# smarty03.net
KiCad netlist of a schematic drawn in EAGLE
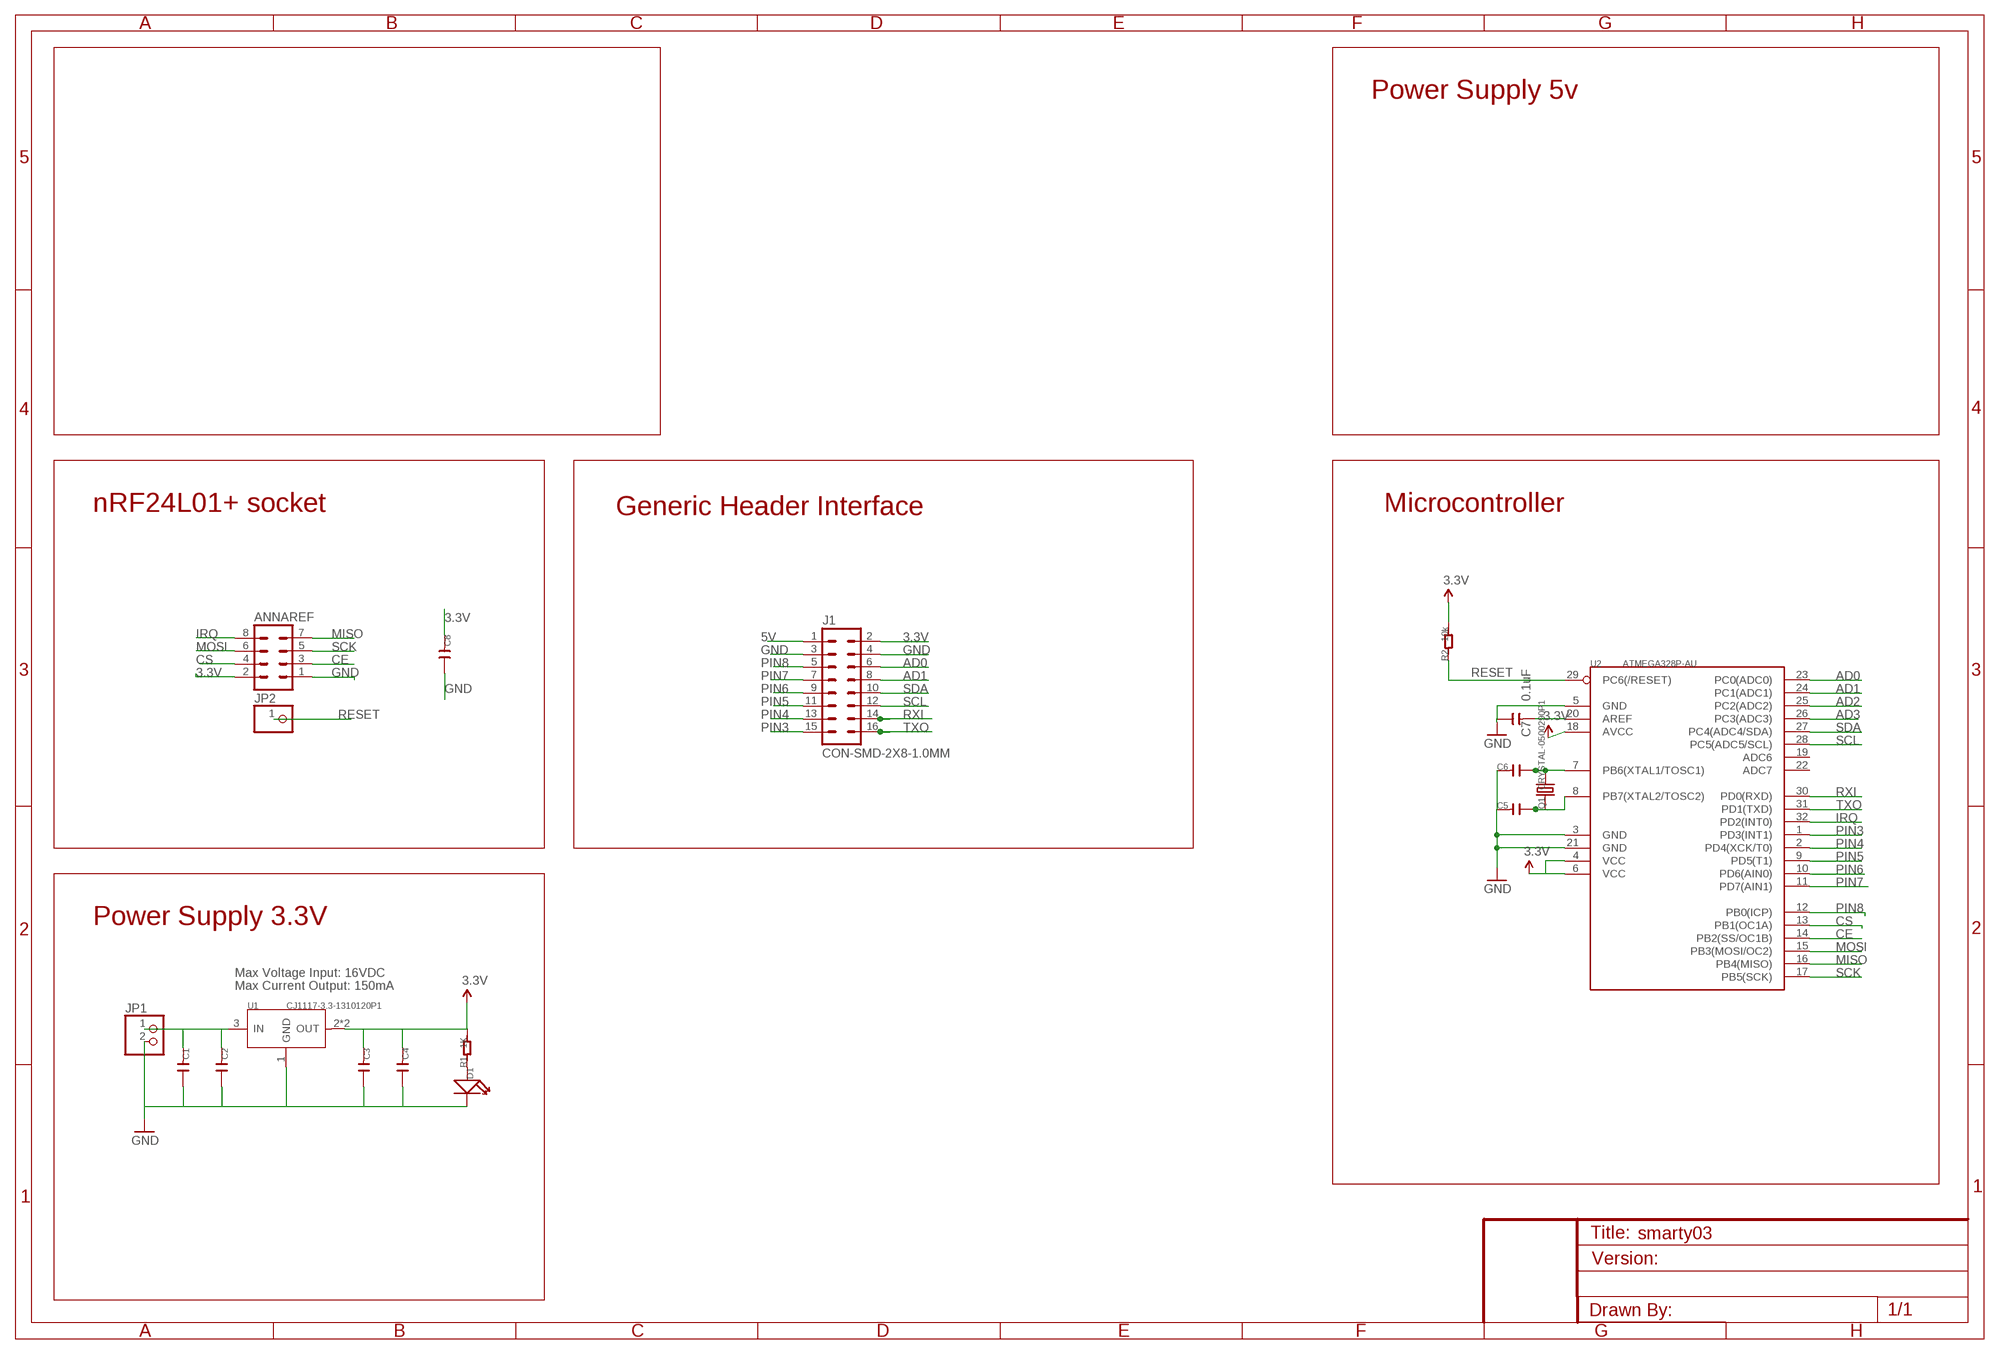
[diagram p0: schematic, sheet 1]

(export (version "E")
  (design (tool "Eeschema 10.0.6"))
  (components
    (comp (ref "ANNAREF")
      (value "MA04-2")
      (footprint "eagle-import:MA04-2")
      (libsource (lib "eagle-import") (part "MA04-2"))
    )
    (comp (ref "C1")
      (value "C-0603")
      (footprint "eagle-import:C0603")
      (libsource (lib "eagle-import") (part "C-0603"))
    )
    (comp (ref "C2")
      (value "C-0805")
      (footprint "eagle-import:C0805")
      (libsource (lib "eagle-import") (part "C-0805"))
    )
    (comp (ref "C3")
      (value "C-0603")
      (footprint "eagle-import:C0603")
      (libsource (lib "eagle-import") (part "C-0603"))
    )
    (comp (ref "C4")
      (value "C-0805")
      (footprint "eagle-import:C0805")
      (libsource (lib "eagle-import") (part "C-0805"))
    )
    (comp (ref "C5")
      (value "C-0603")
      (footprint "eagle-import:C0603")
      (libsource (lib "eagle-import") (part "C-0603"))
    )
    (comp (ref "C6")
      (value "C-0603")
      (footprint "eagle-import:C0603")
      (libsource (lib "eagle-import") (part "C-0603"))
    )
    (comp (ref "C7")
      (value "0.1uF")
      (footprint "eagle-import:C0805")
      (libsource (lib "eagle-import") (part "C-0805"))
    )
    (comp (ref "C8")
      (value "C-0805")
      (footprint "eagle-import:C0805")
      (libsource (lib "eagle-import") (part "C-0805"))
    )
    (comp (ref "D1")
      (value "LED")
      (footprint "eagle-import:LED0603")
      (libsource (lib "eagle-import") (part "LED"))
    )
    (comp (ref "J1")
      (value "CON-SMD-2X8-1.0MM")
      (footprint "eagle-import:SBH100-NBPC-D08")
      (libsource (lib "eagle-import") (part "CON-SMD-2X8-1.0MM"))
    )
    (comp (ref "JP1")
      (value "PINHD-1X2")
      (footprint "eagle-import:1X02")
      (libsource (lib "eagle-import") (part "PINHD-1X2"))
    )
    (comp (ref "JP2")
      (value "PINHD-1X1")
      (footprint "eagle-import:1X01")
      (libsource (lib "eagle-import") (part "PINHD-1X1"))
    )
    (comp (ref "Q1")
      (value "CRYSTAL-0500290P1")
      (footprint "eagle-import:2P-SMD-5.0X3.2")
      (libsource (lib "eagle-import") (part "CRYSTAL-0500290P1"))
    )
    (comp (ref "R1")
      (value "1K")
      (footprint "eagle-import:R0603")
      (libsource (lib "eagle-import") (part "R-0603"))
    )
    (comp (ref "R2")
      (value "10k")
      (footprint "eagle-import:R0603")
      (libsource (lib "eagle-import") (part "R-0603"))
    )
    (comp (ref "U1")
      (value "CJ1117-3.3-1310120P1")
      (footprint "eagle-import:SOT89")
      (libsource (lib "eagle-import") (part "CJ1117-3.3-1310120P1"))
    )
    (comp (ref "U2")
      (value "ATMEGA328P-AU")
      (footprint "eagle-import:TQFP32")
      (libsource (lib "eagle-import") (part "ATMEGA328P-AU-1030060P1"))
    )
  )
  (nets
    (net (code "1") (name "/5V") (class "Default")
      (node (ref "J1") (pin "1") (pinfunction "1_1") (pintype "passive"))
    )
    (net (code "2") (name "/AD0") (class "Default")
      (node (ref "J1") (pin "6") (pinfunction "6_6") (pintype "passive"))
      (node (ref "U2") (pin "23") (pinfunction "PC0(ADC0)_23") (pintype "bidirectional"))
    )
    (net (code "3") (name "/AD1") (class "Default")
      (node (ref "J1") (pin "8") (pinfunction "8_8") (pintype "passive"))
      (node (ref "U2") (pin "24") (pinfunction "PC1(ADC1)_24") (pintype "bidirectional"))
    )
    (net (code "4") (name "/AD2") (class "Default")
      (node (ref "U2") (pin "25") (pinfunction "PC2(ADC2)_25") (pintype "bidirectional"))
    )
    (net (code "5") (name "/AD3") (class "Default")
      (node (ref "U2") (pin "26") (pinfunction "PC3(ADC3)_26") (pintype "bidirectional"))
    )
    (net (code "6") (name "/CE") (class "Default")
      (node (ref "ANNAREF") (pin "3") (pinfunction "3_3") (pintype "passive"))
      (node (ref "U2") (pin "14") (pinfunction "PB2(SS/OC1B)_14") (pintype "bidirectional"))
    )
    (net (code "7") (name "/CS") (class "Default")
      (node (ref "ANNAREF") (pin "4") (pinfunction "4_4") (pintype "passive"))
      (node (ref "U2") (pin "13") (pinfunction "PB1(OC1A)_13") (pintype "bidirectional"))
    )
    (net (code "8") (name "/IRQ") (class "Default")
      (node (ref "ANNAREF") (pin "8") (pinfunction "8_8") (pintype "passive"))
      (node (ref "U2") (pin "32") (pinfunction "PD2(INT0)_32") (pintype "bidirectional"))
    )
    (net (code "9") (name "/MISO") (class "Default")
      (node (ref "ANNAREF") (pin "7") (pinfunction "7_7") (pintype "passive"))
      (node (ref "U2") (pin "16") (pinfunction "PB4(MISO)_16") (pintype "bidirectional"))
    )
    (net (code "10") (name "/MOSI") (class "Default")
      (node (ref "ANNAREF") (pin "6") (pinfunction "6_6") (pintype "passive"))
      (node (ref "U2") (pin "15") (pinfunction "PB3(MOSI/OC2)_15") (pintype "bidirectional"))
    )
    (net (code "11") (name "/PIN3") (class "Default")
      (node (ref "J1") (pin "15") (pinfunction "15_15") (pintype "passive"))
      (node (ref "U2") (pin "1") (pinfunction "PD3(INT1)_1") (pintype "bidirectional"))
    )
    (net (code "12") (name "/PIN4") (class "Default")
      (node (ref "J1") (pin "13") (pinfunction "13_13") (pintype "passive"))
      (node (ref "U2") (pin "2") (pinfunction "PD4(XCK/T0)_2") (pintype "bidirectional"))
    )
    (net (code "13") (name "/PIN5") (class "Default")
      (node (ref "J1") (pin "11") (pinfunction "11_11") (pintype "passive"))
      (node (ref "U2") (pin "9") (pinfunction "PD5(T1)_9") (pintype "bidirectional"))
    )
    (net (code "14") (name "/PIN6") (class "Default")
      (node (ref "J1") (pin "9") (pinfunction "9_9") (pintype "passive"))
      (node (ref "U2") (pin "10") (pinfunction "PD6(AIN0)_10") (pintype "bidirectional"))
    )
    (net (code "15") (name "/PIN7") (class "Default")
      (node (ref "J1") (pin "7") (pinfunction "7_7") (pintype "passive"))
      (node (ref "U2") (pin "11") (pinfunction "PD7(AIN1)_11") (pintype "bidirectional"))
    )
    (net (code "16") (name "/PIN8") (class "Default")
      (node (ref "J1") (pin "5") (pinfunction "5_5") (pintype "passive"))
      (node (ref "U2") (pin "12") (pinfunction "PB0(ICP)_12") (pintype "bidirectional"))
    )
    (net (code "17") (name "/RESET") (class "Default")
      (node (ref "JP2") (pin "1") (pinfunction "1_1") (pintype "passive"))
      (node (ref "R2") (pin "1") (pinfunction "1_1") (pintype "bidirectional"))
      (node (ref "U2") (pin "29") (pinfunction "PC6(/RESET)_29") (pintype "bidirectional"))
    )
    (net (code "18") (name "/RXI") (class "Default")
      (node (ref "J1") (pin "14") (pinfunction "14_14") (pintype "passive"))
      (node (ref "U2") (pin "30") (pinfunction "PD0(RXD)_30") (pintype "bidirectional"))
    )
    (net (code "19") (name "/SCK") (class "Default")
      (node (ref "ANNAREF") (pin "5") (pinfunction "5_5") (pintype "passive"))
      (node (ref "U2") (pin "17") (pinfunction "PB5(SCK)_17") (pintype "bidirectional"))
    )
    (net (code "20") (name "/SCL") (class "Default")
      (node (ref "J1") (pin "12") (pinfunction "12_12") (pintype "passive"))
      (node (ref "U2") (pin "28") (pinfunction "PC5(ADC5/SCL)_28") (pintype "bidirectional"))
    )
    (net (code "21") (name "/SDA") (class "Default")
      (node (ref "J1") (pin "10") (pinfunction "10_10") (pintype "passive"))
      (node (ref "U2") (pin "27") (pinfunction "PC4(ADC4/SDA)_27") (pintype "bidirectional"))
    )
    (net (code "22") (name "/TXO") (class "Default")
      (node (ref "J1") (pin "16") (pinfunction "16_16") (pintype "passive"))
      (node (ref "U2") (pin "31") (pinfunction "PD1(TXD)_31") (pintype "bidirectional"))
    )
    (net (code "23") (name "3.3V") (class "Default")
      (node (ref "ANNAREF") (pin "2") (pinfunction "2_2") (pintype "passive"))
      (node (ref "C3") (pin "1") (pinfunction "1_1") (pintype "bidirectional"))
      (node (ref "C4") (pin "1") (pinfunction "1_1") (pintype "bidirectional"))
      (node (ref "C8") (pin "1") (pinfunction "1_1") (pintype "bidirectional"))
      (node (ref "J1") (pin "2") (pinfunction "2_2") (pintype "passive"))
      (node (ref "R1") (pin "2") (pinfunction "2_2") (pintype "bidirectional"))
      (node (ref "R2") (pin "2") (pinfunction "2_2") (pintype "bidirectional"))
      (node (ref "U1") (pin "2") (pinfunction "OUT_2") (pintype "bidirectional"))
      (node (ref "U1") (pin "4") (pinfunction "OUT_4") (pintype "bidirectional"))
      (node (ref "U2") (pin "18") (pinfunction "AVCC_18") (pintype "bidirectional"))
      (node (ref "U2") (pin "4") (pinfunction "VCC_4") (pintype "bidirectional"))
      (node (ref "U2") (pin "6") (pinfunction "VCC_6") (pintype "bidirectional"))
    )
    (net (code "24") (name "GND") (class "Default")
      (node (ref "ANNAREF") (pin "1") (pinfunction "1_1") (pintype "passive"))
      (node (ref "C1") (pin "2") (pinfunction "2_2") (pintype "bidirectional"))
      (node (ref "C2") (pin "2") (pinfunction "2_2") (pintype "bidirectional"))
      (node (ref "C3") (pin "2") (pinfunction "2_2") (pintype "bidirectional"))
      (node (ref "C4") (pin "2") (pinfunction "2_2") (pintype "bidirectional"))
      (node (ref "C5") (pin "1") (pinfunction "1_1") (pintype "bidirectional"))
      (node (ref "C6") (pin "1") (pinfunction "1_1") (pintype "bidirectional"))
      (node (ref "C7") (pin "2") (pinfunction "2_2") (pintype "bidirectional"))
      (node (ref "C8") (pin "2") (pinfunction "2_2") (pintype "bidirectional"))
      (node (ref "D1") (pin "-") (pinfunction "-_-") (pintype "passive"))
      (node (ref "J1") (pin "3") (pinfunction "3_3") (pintype "passive"))
      (node (ref "J1") (pin "4") (pinfunction "4_4") (pintype "passive"))
      (node (ref "JP1") (pin "2") (pinfunction "2_2") (pintype "passive"))
      (node (ref "U1") (pin "1") (pinfunction "GND_1") (pintype "bidirectional"))
      (node (ref "U2") (pin "21") (pinfunction "GND_21") (pintype "bidirectional"))
      (node (ref "U2") (pin "3") (pinfunction "GND_3") (pintype "bidirectional"))
      (node (ref "U2") (pin "5") (pinfunction "GND_5") (pintype "bidirectional"))
    )
    (net (code "25") (name "Net-(D1-Pad+)") (class "Default")
      (node (ref "D1") (pin "+") (pinfunction "+_+") (pintype "passive"))
      (node (ref "R1") (pin "1") (pinfunction "1_1") (pintype "bidirectional"))
    )
    (net (code "26") (name "Net-(U1-IN)") (class "Default")
      (node (ref "C1") (pin "1") (pinfunction "1_1") (pintype "bidirectional"))
      (node (ref "C2") (pin "1") (pinfunction "1_1") (pintype "bidirectional"))
      (node (ref "JP1") (pin "1") (pinfunction "1_1") (pintype "passive"))
      (node (ref "U1") (pin "3") (pinfunction "IN_3") (pintype "bidirectional"))
    )
    (net (code "27") (name "Net-(U2-AREF)") (class "Default")
      (node (ref "C7") (pin "1") (pinfunction "1_1") (pintype "bidirectional"))
      (node (ref "U2") (pin "20") (pinfunction "AREF_20") (pintype "bidirectional"))
    )
    (net (code "28") (name "Net-(U2-PB6(XTAL1{slash}TOSC1))") (class "Default")
      (node (ref "C6") (pin "2") (pinfunction "2_2") (pintype "bidirectional"))
      (node (ref "Q1") (pin "2") (pinfunction "2_2") (pintype "passive"))
      (node (ref "U2") (pin "7") (pinfunction "PB6(XTAL1/TOSC1)_7") (pintype "bidirectional"))
    )
    (net (code "29") (name "Net-(U2-PB7(XTAL2{slash}TOSC2))") (class "Default")
      (node (ref "C5") (pin "2") (pinfunction "2_2") (pintype "bidirectional"))
      (node (ref "Q1") (pin "1") (pinfunction "1_1") (pintype "passive"))
      (node (ref "U2") (pin "8") (pinfunction "PB7(XTAL2/TOSC2)_8") (pintype "bidirectional"))
    )
    (net (code "30") (name "unconnected-(U2-ADC6-Pad19)") (class "Default")
      (node (ref "U2") (pin "19") (pinfunction "ADC6_19") (pintype "bidirectional"))
    )
    (net (code "31") (name "unconnected-(U2-ADC7-Pad22)") (class "Default")
      (node (ref "U2") (pin "22") (pinfunction "ADC7_22") (pintype "bidirectional"))
    )
  )
)
